# LAN8742AI-CZ-TR.net
KiCad netlist of a schematic drawn in Altium Designer
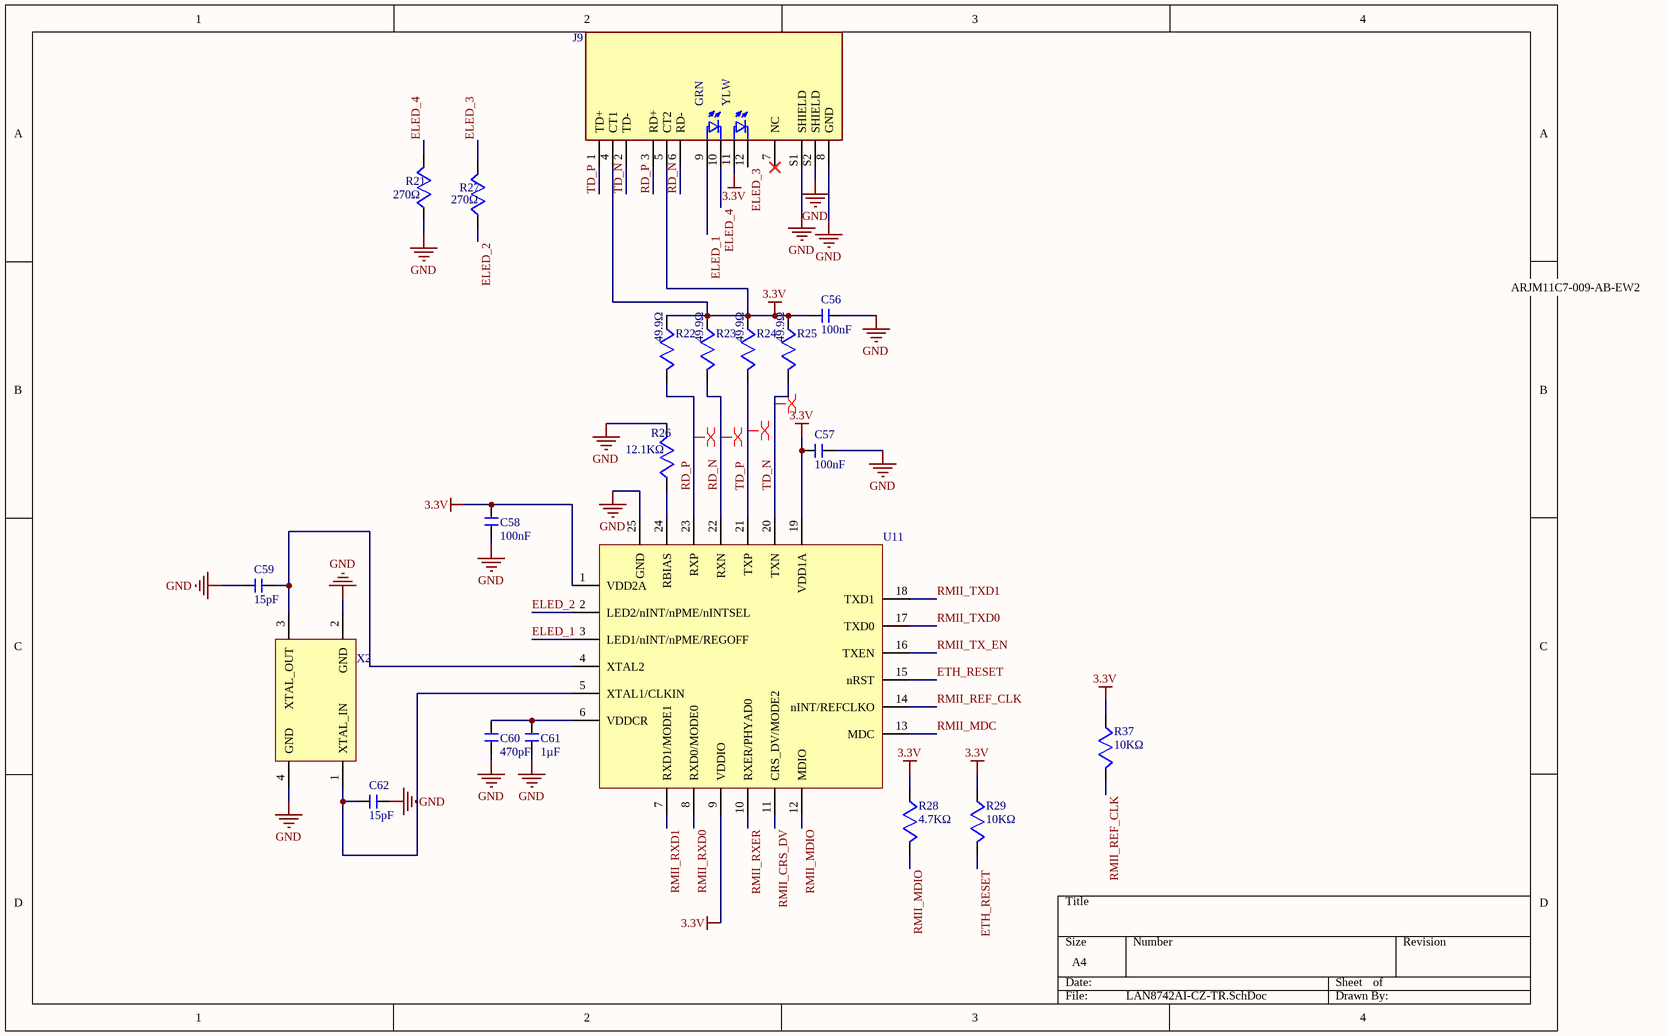
[diagram p0: LAN8742AI-CZ-TR.SchDoc]

(export (version "E")
  (design (tool "Eeschema 10.0.6"))
  (components
    (comp (ref "C56")
      (value "100nF")
      (footprint "402 capacitor - duplicate")
      (description "CAP SMD 402")
      (fields (field (name "MPN") "CL05A104KA5NNNC") (field (name "Comment") "0402 capacitor"))
      (libsource (lib "Schlib1") (part "CAP SMD 402"))
    )
    (comp (ref "C57")
      (value "100nF")
      (footprint "402 capacitor - duplicate")
      (description "CAP SMD 402")
      (fields (field (name "MPN") "CL05A104KA5NNNC") (field (name "Comment") "0402 capacitor"))
      (libsource (lib "Schlib1") (part "CAP SMD 402"))
    )
    (comp (ref "C58")
      (value "100nF")
      (footprint "402 capacitor - duplicate")
      (description "CAP SMD 402")
      (fields (field (name "MPN") "CL05A104KA5NNNC") (field (name "Comment") "0402 capacitor"))
      (libsource (lib "Schlib1") (part "CAP SMD 402"))
    )
    (comp (ref "C59")
      (value "15pF")
      (footprint "402 capacitor - duplicate")
      (description "CAP SMD 402")
      (fields (field (name "MPN") "GRM1555C1H150JA01D") (field (name "Comment") "0402 capacitor"))
      (libsource (lib "Schlib1") (part "CAP SMD 402"))
    )
    (comp (ref "C60")
      (value "470pF")
      (footprint "402 capacitor - duplicate")
      (description "CAP SMD 402")
      (fields (field (name "MPN") "GRM1555C1H471JA01D") (field (name "Comment") "0402 capacitor"))
      (libsource (lib "Schlib1") (part "CAP SMD 402"))
    )
    (comp (ref "C61")
      (value "1µF")
      (footprint "402 capacitor - duplicate")
      (description "CAP SMD 402")
      (fields (field (name "MPN") "GRM155R6YA105KE11D") (field (name "Comment") "0402 capacitor"))
      (libsource (lib "Schlib1") (part "CAP SMD 402"))
    )
    (comp (ref "C62")
      (value "15pF")
      (footprint "402 capacitor - duplicate")
      (description "CAP SMD 402")
      (fields (field (name "MPN") "GRM1555C1H150JA01D") (field (name "Comment") "0402 capacitor"))
      (libsource (lib "Schlib1") (part "CAP SMD 402"))
    )
    (comp (ref "J9")
      (value "ARJM11C7-009-AB-EW2")
      (footprint "ARJM11C7-009-AB-EW2")
      (description "CONN JACK 1PORT PCB")
      (libsource (lib "Schlib1") (part "ARJM11C7-009-AB-EW2"))
    )
    (comp (ref "R21")
      (value "270Ω")
      (footprint "402 RESISTOR")
      (description "RES SMD 0402")
      (fields (field (name "MPN") "RMCF0402FT270R") (field (name "Comment") "0402. RESİSTOR"))
      (libsource (lib "Schlib1") (part "RES SMD 0402"))
    )
    (comp (ref "R22")
      (value "49.9Ω")
      (footprint "402 RESISTOR")
      (description "RES SMD 0402")
      (fields (field (name "MPN") "RG1005N-49R9-W-T1") (field (name "Comment") "0402. RESİSTOR"))
      (libsource (lib "Schlib1") (part "RES SMD 0402"))
    )
    (comp (ref "R23")
      (value "49.9Ω")
      (footprint "402 RESISTOR")
      (description "RES SMD 0402")
      (fields (field (name "MPN") "RG1005N-49R9-W-T1") (field (name "Comment") "0402. RESİSTOR"))
      (libsource (lib "Schlib1") (part "RES SMD 0402"))
    )
    (comp (ref "R24")
      (value "49.9Ω")
      (footprint "402 RESISTOR")
      (description "RES SMD 0402")
      (fields (field (name "MPN") "RG1005N-49R9-W-T1") (field (name "Comment") "0402. RESİSTOR"))
      (libsource (lib "Schlib1") (part "RES SMD 0402"))
    )
    (comp (ref "R25")
      (value "49.9Ω")
      (footprint "402 RESISTOR")
      (description "RES SMD 0402")
      (fields (field (name "MPN") "RG1005N-49R9-W-T1") (field (name "Comment") "0402. RESİSTOR"))
      (libsource (lib "Schlib1") (part "RES SMD 0402"))
    )
    (comp (ref "R26")
      (value "12.1KΩ")
      (footprint "603 resistor")
      (description "RES SMD 0603")
      (fields (field (name "MPN") "RT0603BRD0712K1L") (field (name "Comment") "0603 RESİSTOR"))
      (libsource (lib "Schlib1") (part "RES SMD 0603"))
    )
    (comp (ref "R27")
      (value "270Ω")
      (footprint "402 RESISTOR")
      (description "RES SMD 0402")
      (fields (field (name "MPN") "RMCF0402FT270R") (field (name "Comment") "0402. RESİSTOR"))
      (libsource (lib "Schlib1") (part "RES SMD 0402"))
    )
    (comp (ref "R28")
      (value "4.7KΩ")
      (footprint "402 RESISTOR")
      (description "RES SMD 0402")
      (fields (field (name "MPN") "RMCF0402FT4K70") (field (name "Comment") "0402. RESİSTOR"))
      (libsource (lib "Schlib1") (part "RES SMD 0402"))
    )
    (comp (ref "R29")
      (value "10KΩ")
      (footprint "402 RESISTOR")
      (description "RES SMD 0402")
      (fields (field (name "MPN") "RNCF0402BTE10K0") (field (name "Comment") "0402. RESİSTOR"))
      (libsource (lib "Schlib1") (part "RES SMD 0402"))
    )
    (comp (ref "R37")
      (value "10KΩ")
      (footprint "402 RESISTOR")
      (description "RES SMD 0402")
      (fields (field (name "MPN") "RNCF0402BTE10K0") (field (name "Comment") "0402. RESİSTOR"))
      (libsource (lib "Schlib1") (part "RES SMD 0402"))
    )
    (comp (ref "U11")
      (value "LAN8742AI-CZ-TR")
      (footprint "LAN8742AI-CZ-TR")
      (description "IC TRANSCEIVER FULL 1/1 24SQFN")
      (libsource (lib "Schlib1") (part "LAN8742AI-CZ-TR"))
    )
    (comp (ref "X2")
      (value "RH100-25.000-10-F-1010-EXT-TR")
      (footprint "RH100-25.000-10-F-1010-EXT-TR")
      (description "CRYSTAL 25.0000MHZ 10PF SMD")
      (libsource (lib "Schlib1") (part "RH100-25.000-10-F-1010-EXT-TR"))
    )
  )
  (nets
    (net (code "1") (name "/ELED_1") (class "Default")
      (node (ref "J9") (pin "9") (pinfunction "9_9") (pintype "passive"))
      (node (ref "U11") (pin "3") (pinfunction "LED1/nINT/nPME/REGOFF_3") (pintype "passive"))
    )
    (net (code "2") (name "/ELED_2") (class "Default")
      (node (ref "R27") (pin "1") (pintype "passive"))
      (node (ref "U11") (pin "2") (pinfunction "LED2/nINT/nPME/nINTSEL_2") (pintype "passive"))
    )
    (net (code "3") (name "/ELED_3") (class "Default")
      (node (ref "J9") (pin "12") (pinfunction "12_12") (pintype "passive"))
      (node (ref "R27") (pin "2") (pintype "passive"))
    )
    (net (code "4") (name "/ELED_4") (class "Default")
      (node (ref "J9") (pin "10") (pinfunction "10_10") (pintype "passive"))
      (node (ref "R21") (pin "2") (pintype "passive"))
    )
    (net (code "5") (name "/ETH_RESET") (class "Default")
      (node (ref "R29") (pin "2") (pintype "passive"))
      (node (ref "U11") (pin "15") (pinfunction "nRST_15") (pintype "passive"))
    )
    (net (code "6") (name "/RD_N") (class "Default")
      (node (ref "J9") (pin "6") (pinfunction "RD-_6") (pintype "passive"))
      (node (ref "R23") (pin "2") (pintype "passive"))
      (node (ref "U11") (pin "22") (pinfunction "RXN_22") (pintype "passive"))
    )
    (net (code "7") (name "/RD_P") (class "Default")
      (node (ref "J9") (pin "3") (pinfunction "RD+_3") (pintype "passive"))
      (node (ref "R22") (pin "2") (pintype "passive"))
      (node (ref "U11") (pin "23") (pinfunction "RXP_23") (pintype "passive"))
    )
    (net (code "8") (name "/RMII_CRS_DV") (class "Default")
      (node (ref "U11") (pin "11") (pinfunction "CRS_DV/MODE2_11") (pintype "passive"))
    )
    (net (code "9") (name "/RMII_MDC") (class "Default")
      (node (ref "U11") (pin "13") (pinfunction "MDC_13") (pintype "passive"))
    )
    (net (code "10") (name "/RMII_MDIO") (class "Default")
      (node (ref "R28") (pin "2") (pintype "passive"))
      (node (ref "U11") (pin "12") (pinfunction "MDIO_12") (pintype "passive"))
    )
    (net (code "11") (name "/RMII_REF_CLK") (class "Default")
      (node (ref "R37") (pin "2") (pintype "passive"))
      (node (ref "U11") (pin "14") (pinfunction "nINT/REFCLKO_14") (pintype "passive"))
    )
    (net (code "12") (name "/RMII_RXD0") (class "Default")
      (node (ref "U11") (pin "8") (pinfunction "RXD0/MODE0_8") (pintype "passive"))
    )
    (net (code "13") (name "/RMII_RXD1") (class "Default")
      (node (ref "U11") (pin "7") (pinfunction "RXD1/MODE1_7") (pintype "passive"))
    )
    (net (code "14") (name "/RMII_RXER") (class "Default")
      (node (ref "U11") (pin "10") (pinfunction "RXER/PHYAD0_10") (pintype "passive"))
    )
    (net (code "15") (name "/RMII_TXD0") (class "Default")
      (node (ref "U11") (pin "17") (pinfunction "TXD0_17") (pintype "passive"))
    )
    (net (code "16") (name "/RMII_TXD1") (class "Default")
      (node (ref "U11") (pin "18") (pinfunction "TXD1_18") (pintype "passive"))
    )
    (net (code "17") (name "/RMII_TX_EN") (class "Default")
      (node (ref "U11") (pin "16") (pinfunction "TXEN_16") (pintype "passive"))
    )
    (net (code "18") (name "/TD_N") (class "Default")
      (node (ref "J9") (pin "2") (pinfunction "TD-_2") (pintype "passive"))
      (node (ref "R25") (pin "2") (pintype "passive"))
      (node (ref "U11") (pin "20") (pinfunction "TXN_20") (pintype "passive"))
    )
    (net (code "19") (name "/TD_P") (class "Default")
      (node (ref "J9") (pin "1") (pinfunction "TD+_1") (pintype "passive"))
      (node (ref "R24") (pin "2") (pintype "passive"))
      (node (ref "U11") (pin "21") (pinfunction "TXP_21") (pintype "passive"))
    )
    (net (code "20") (name "3.3V") (class "Default")
      (node (ref "C56") (pin "1") (pintype "passive"))
      (node (ref "C57") (pin "2") (pintype "passive"))
      (node (ref "C58") (pin "2") (pintype "passive"))
      (node (ref "J9") (pin "11") (pinfunction "11_11") (pintype "passive"))
      (node (ref "J9") (pin "4") (pinfunction "CT1_4") (pintype "passive"))
      (node (ref "J9") (pin "5") (pinfunction "CT2_5") (pintype "passive"))
      (node (ref "R22") (pin "1") (pintype "passive"))
      (node (ref "R23") (pin "1") (pintype "passive"))
      (node (ref "R24") (pin "1") (pintype "passive"))
      (node (ref "R25") (pin "1") (pintype "passive"))
      (node (ref "R28") (pin "1") (pintype "passive"))
      (node (ref "R29") (pin "1") (pintype "passive"))
      (node (ref "R37") (pin "1") (pintype "passive"))
      (node (ref "U11") (pin "1") (pinfunction "VDD2A_1") (pintype "passive"))
      (node (ref "U11") (pin "19") (pinfunction "VDD1A_19") (pintype "passive"))
      (node (ref "U11") (pin "9") (pinfunction "VDDIO_9") (pintype "passive"))
    )
    (net (code "21") (name "GND") (class "Default")
      (node (ref "C56") (pin "2") (pintype "passive"))
      (node (ref "C57") (pin "1") (pintype "passive"))
      (node (ref "C58") (pin "1") (pintype "passive"))
      (node (ref "C59") (pin "1") (pintype "passive"))
      (node (ref "C60") (pin "1") (pintype "passive"))
      (node (ref "C61") (pin "1") (pintype "passive"))
      (node (ref "C62") (pin "1") (pintype "passive"))
      (node (ref "J9") (pin "8") (pinfunction "GND_8") (pintype "power_in"))
      (node (ref "J9") (pin "S1") (pinfunction "SHIELD_S1") (pintype "passive"))
      (node (ref "J9") (pin "S2") (pinfunction "SHIELD_S2") (pintype "passive"))
      (node (ref "R21") (pin "1") (pintype "passive"))
      (node (ref "R26") (pin "2") (pintype "passive"))
      (node (ref "U11") (pin "25") (pinfunction "GND_25") (pintype "passive"))
      (node (ref "X2") (pin "2") (pinfunction "GND_2") (pintype "passive"))
      (node (ref "X2") (pin "4") (pinfunction "GND_4") (pintype "passive"))
    )
    (net (code "22") (name "Net-(U11-RBIAS)") (class "Default")
      (node (ref "R26") (pin "1") (pintype "passive"))
      (node (ref "U11") (pin "24") (pinfunction "RBIAS_24") (pintype "passive"))
    )
    (net (code "23") (name "Net-(U11-VDDCR)") (class "Default")
      (node (ref "C60") (pin "2") (pintype "passive"))
      (node (ref "C61") (pin "2") (pintype "passive"))
      (node (ref "U11") (pin "6") (pinfunction "VDDCR_6") (pintype "passive"))
    )
    (net (code "24") (name "Net-(U11-XTAL1{slash}CLKIN)") (class "Default")
      (node (ref "C62") (pin "2") (pintype "passive"))
      (node (ref "U11") (pin "5") (pinfunction "XTAL1/CLKIN_5") (pintype "passive"))
      (node (ref "X2") (pin "1") (pinfunction "XTAL_IN_1") (pintype "passive"))
    )
    (net (code "25") (name "Net-(U11-XTAL2)") (class "Default")
      (node (ref "C59") (pin "2") (pintype "passive"))
      (node (ref "U11") (pin "4") (pinfunction "XTAL2_4") (pintype "passive"))
      (node (ref "X2") (pin "3") (pinfunction "XTAL_OUT_3") (pintype "passive"))
    )
    (net (code "26") (name "unconnected-(J9-NC-Pad7)") (class "Default")
      (node (ref "J9") (pin "7") (pinfunction "NC_7") (pintype "passive+no_connect"))
    )
  )
)
